# psu.net
KiCad netlist of a schematic drawn in EAGLE
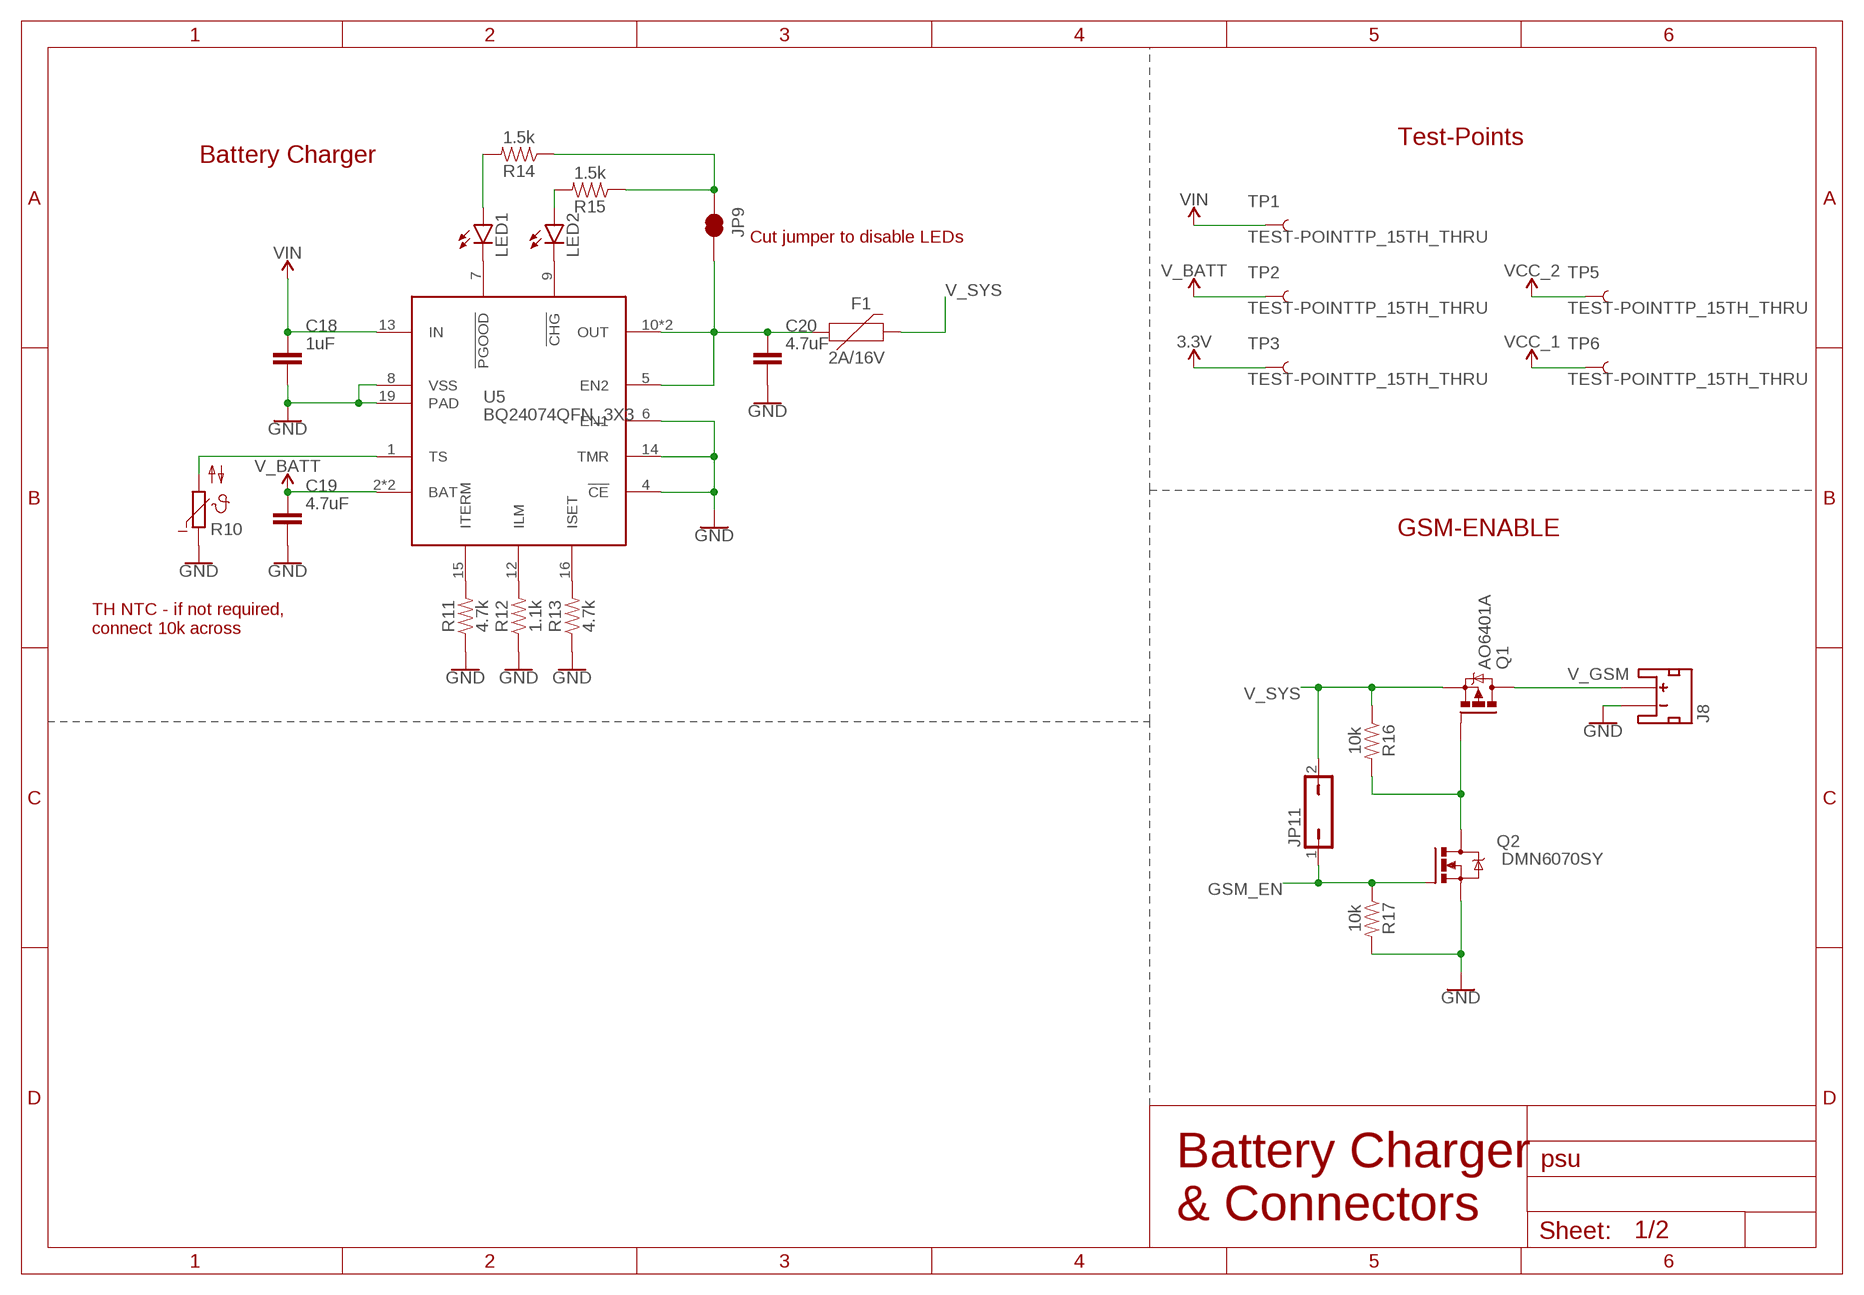
[diagram p0: schematic, sheet 1]
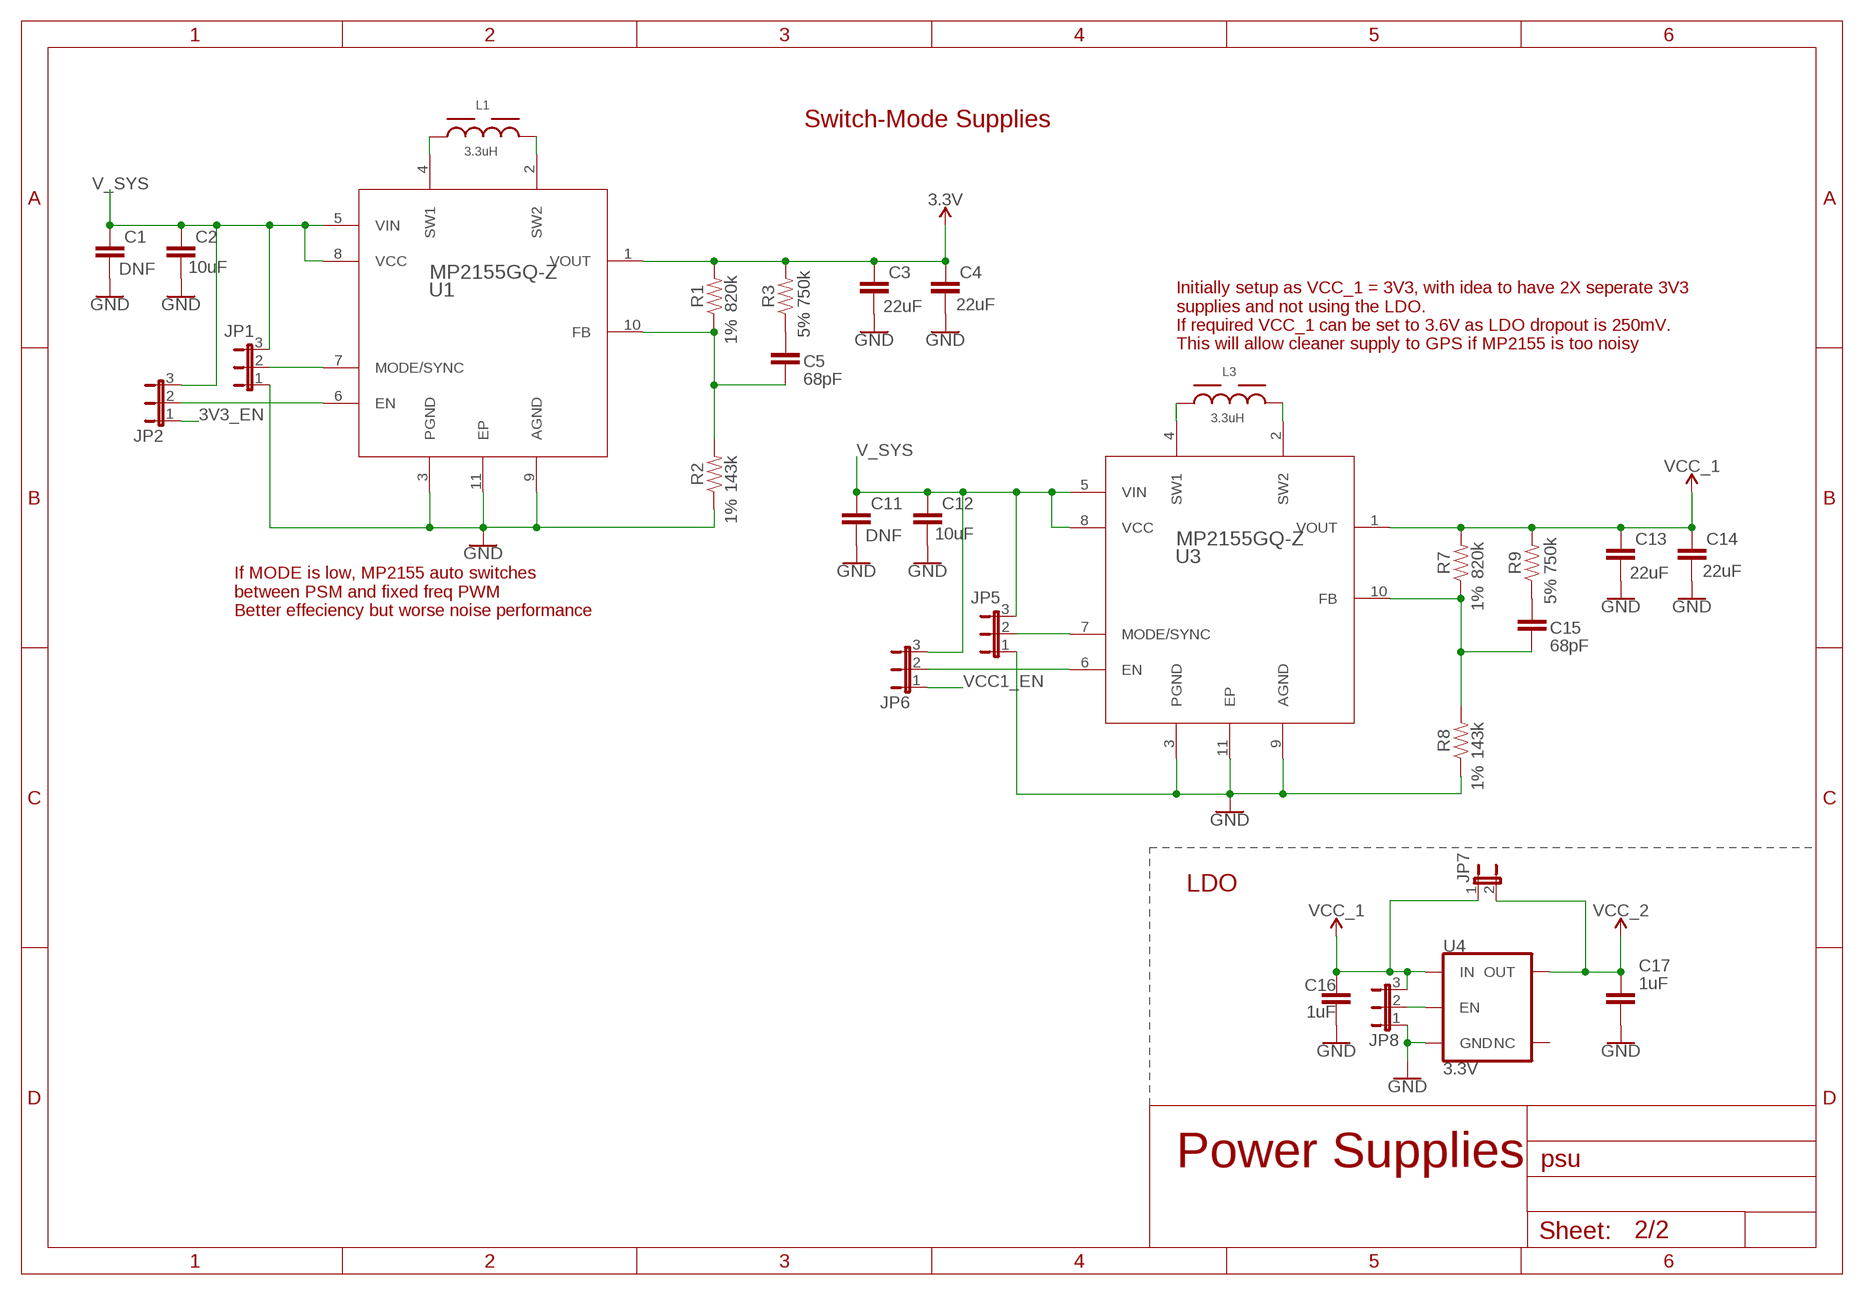
[diagram p1: schematic, sheet 2]

(export (version "E")
  (design (tool "Eeschema 10.0.6"))
  (components
    (comp (ref "C18")
      (value "1uF")
      (footprint "eagle-import:CAPC2012X110")
      (libsource (lib "eagle-import") (part "CCHIP-0805(2012-METRIC)_"))
    )
    (comp (ref "C19")
      (value "4.7uF")
      (footprint "eagle-import:CAPC2012X110")
      (libsource (lib "eagle-import") (part "CCHIP-0805(2012-METRIC)_"))
    )
    (comp (ref "C20")
      (value "4.7uF")
      (footprint "eagle-import:CAPC2012X110")
      (libsource (lib "eagle-import") (part "CCHIP-0805(2012-METRIC)_"))
    )
    (comp (ref "F1")
      (value "2A/16V")
      (footprint "eagle-import:F1812")
      (libsource (lib "eagle-import") (part "PPTC_2A"))
    )
    (comp (ref "J8")
      (value "JST_2MM_MALE")
      (footprint "eagle-import:JST-2-SMD")
      (libsource (lib "eagle-import") (part "JST_2MM_MALE"))
    )
    (comp (ref "JP9")
      (value "JUMPER-SMT_2_NC_TRACE_SILK")
      (footprint "eagle-import:SMT-JUMPER_2_NC_TRACE_SILK")
      (libsource (lib "eagle-import") (part "JUMPER-SMT_2_NC_TRACE_SILK"))
    )
    (comp (ref "JP11")
      (value "JP1Q")
      (footprint "eagle-import:JP1")
      (libsource (lib "eagle-import") (part "JP1Q"))
    )
    (comp (ref "LED1")
      (value "LEDSML0805")
      (footprint "eagle-import:SML0805")
      (libsource (lib "eagle-import") (part "LEDSML0805"))
    )
    (comp (ref "LED2")
      (value "LEDSML0805")
      (footprint "eagle-import:SML0805")
      (libsource (lib "eagle-import") (part "LEDSML0805"))
    )
    (comp (ref "Q1")
      (value "AO6401A")
      (footprint "eagle-import:TSOP-6")
      (libsource (lib "eagle-import") (part "AO6401A"))
    )
    (comp (ref "Q2")
      (value "DMN6070SY")
      (footprint "eagle-import:SOT-89-3")
      (libsource (lib "eagle-import") (part "DMN6070SY-13"))
    )
    (comp (ref "R10")
      (value "DNF")
      (footprint "eagle-import:P640")
      (libsource (lib "eagle-import") (part "NTC640"))
    )
    (comp (ref "R11")
      (value "4.7k")
      (footprint "eagle-import:0603")
      (libsource (lib "eagle-import") (part "RESISTOR0603"))
    )
    (comp (ref "R12")
      (value "1.1k")
      (footprint "eagle-import:0603")
      (libsource (lib "eagle-import") (part "RESISTOR0603"))
    )
    (comp (ref "R13")
      (value "4.7k")
      (footprint "eagle-import:0603")
      (libsource (lib "eagle-import") (part "RESISTOR0603"))
    )
    (comp (ref "R14")
      (value "1.5k")
      (footprint "eagle-import:0603")
      (libsource (lib "eagle-import") (part "RESISTOR0603"))
    )
    (comp (ref "R15")
      (value "1.5k")
      (footprint "eagle-import:0603")
      (libsource (lib "eagle-import") (part "RESISTOR0603"))
    )
    (comp (ref "R16")
      (value "10k")
      (footprint "eagle-import:0603")
      (libsource (lib "eagle-import") (part "RESISTOR0603"))
    )
    (comp (ref "R17")
      (value "10k")
      (footprint "eagle-import:0603")
      (libsource (lib "eagle-import") (part "RESISTOR0603"))
    )
    (comp (ref "TP1")
      (value "TEST-POINTTP_15TH_THRU")
      (footprint "eagle-import:TP_15TH")
      (libsource (lib "eagle-import") (part "TEST-POINTTP_15TH_THRU"))
    )
    (comp (ref "TP2")
      (value "TEST-POINTTP_15TH_THRU")
      (footprint "eagle-import:TP_15TH")
      (libsource (lib "eagle-import") (part "TEST-POINTTP_15TH_THRU"))
    )
    (comp (ref "TP3")
      (value "TEST-POINTTP_15TH_THRU")
      (footprint "eagle-import:TP_15TH")
      (libsource (lib "eagle-import") (part "TEST-POINTTP_15TH_THRU"))
    )
    (comp (ref "TP5")
      (value "TEST-POINTTP_15TH_THRU")
      (footprint "eagle-import:TP_15TH")
      (libsource (lib "eagle-import") (part "TEST-POINTTP_15TH_THRU"))
    )
    (comp (ref "TP6")
      (value "TEST-POINTTP_15TH_THRU")
      (footprint "eagle-import:TP_15TH")
      (libsource (lib "eagle-import") (part "TEST-POINTTP_15TH_THRU"))
    )
    (comp (ref "U5")
      (value "BQ24074QFN_3X3")
      (footprint "eagle-import:QFN_3X3")
      (libsource (lib "eagle-import") (part "BQ24074QFN_3X3"))
    )
    (comp (ref "C1")
      (value "DNF")
      (footprint "eagle-import:CAPC2012X110")
      (libsource (lib "eagle-import") (part "CCHIP-0805(2012-METRIC)_"))
    )
    (comp (ref "C2")
      (value "10uF")
      (footprint "eagle-import:CAPC2012X110")
      (fields (field (name "TYPE") "X7R") (field (name "VOLTAGE_RATING") "6.3V"))
      (libsource (lib "eagle-import") (part "CCHIP-0805(2012-METRIC)_"))
    )
    (comp (ref "C3")
      (value "22uF")
      (footprint "eagle-import:CAPC2012X110")
      (fields (field (name "TYPE") "X5R") (field (name "VOLTAGE_RATING") "10V"))
      (libsource (lib "eagle-import") (part "CCHIP-0805(2012-METRIC)_"))
    )
    (comp (ref "C4")
      (value "22uF")
      (footprint "eagle-import:CAPC2012X110")
      (fields (field (name "TYPE") "X5R") (field (name "VOLTAGE_RATING") "10V"))
      (libsource (lib "eagle-import") (part "CCHIP-0805(2012-METRIC)_"))
    )
    (comp (ref "C5")
      (value "68pF")
      (footprint "eagle-import:CAPC1608X85")
      (fields (field (name "TYPE") "X7R") (field (name "VOLTAGE_RATING") "50V"))
      (libsource (lib "eagle-import") (part "CCHIP-0603(1608-METRIC)_"))
    )
    (comp (ref "C11")
      (value "DNF")
      (footprint "eagle-import:CAPC2012X110")
      (libsource (lib "eagle-import") (part "CCHIP-0805(2012-METRIC)_"))
    )
    (comp (ref "C12")
      (value "10uF")
      (footprint "eagle-import:CAPC2012X110")
      (fields (field (name "TYPE") "X7R") (field (name "VOLTAGE_RATING") "6.3V"))
      (libsource (lib "eagle-import") (part "CCHIP-0805(2012-METRIC)_"))
    )
    (comp (ref "C13")
      (value "22uF")
      (footprint "eagle-import:CAPC2012X110")
      (fields (field (name "TYPE") "X5R") (field (name "VOLTAGE_RATING") "10V"))
      (libsource (lib "eagle-import") (part "CCHIP-0805(2012-METRIC)_"))
    )
    (comp (ref "C14")
      (value "22uF")
      (footprint "eagle-import:CAPC2012X110")
      (fields (field (name "TYPE") "X5R") (field (name "VOLTAGE_RATING") "10V"))
      (libsource (lib "eagle-import") (part "CCHIP-0805(2012-METRIC)_"))
    )
    (comp (ref "C15")
      (value "68pF")
      (footprint "eagle-import:CAPC1608X85")
      (fields (field (name "TYPE") "X7R") (field (name "VOLTAGE_RATING") "50V"))
      (libsource (lib "eagle-import") (part "CCHIP-0603(1608-METRIC)_"))
    )
    (comp (ref "C16")
      (value "1uF")
      (footprint "eagle-import:CAPC2012X110")
      (libsource (lib "eagle-import") (part "CCHIP-0805(2012-METRIC)_"))
    )
    (comp (ref "C17")
      (value "1uF")
      (footprint "eagle-import:CAPC2012X110")
      (libsource (lib "eagle-import") (part "CCHIP-0805(2012-METRIC)_"))
    )
    (comp (ref "JP1")
      (value "JP2E")
      (footprint "eagle-import:JP2")
      (libsource (lib "eagle-import") (part "JP2E"))
    )
    (comp (ref "JP2")
      (value "JP2E")
      (footprint "eagle-import:JP2")
      (libsource (lib "eagle-import") (part "JP2E"))
    )
    (comp (ref "JP5")
      (value "JP2E")
      (footprint "eagle-import:JP2")
      (libsource (lib "eagle-import") (part "JP2E"))
    )
    (comp (ref "JP6")
      (value "JP2E")
      (footprint "eagle-import:JP2")
      (libsource (lib "eagle-import") (part "JP2E"))
    )
    (comp (ref "JP7")
      (value "JP1E")
      (footprint "eagle-import:JP1")
      (libsource (lib "eagle-import") (part "JP1E"))
    )
    (comp (ref "JP8")
      (value "JP2E")
      (footprint "eagle-import:JP2")
      (libsource (lib "eagle-import") (part "JP2E"))
    )
    (comp (ref "L1")
      (value "3.3uH")
      (footprint "eagle-import:WE-HCI_7050")
      (libsource (lib "eagle-import") (part "WE-HCI_7050_744314330"))
    )
    (comp (ref "L3")
      (value "3.3uH")
      (footprint "eagle-import:WE-HCI_7050")
      (libsource (lib "eagle-import") (part "WE-HCI_7050_744314330"))
    )
    (comp (ref "R1")
      (value "820k")
      (footprint "eagle-import:0603")
      (fields (field (name "TOLERANCE") "1%"))
      (libsource (lib "eagle-import") (part "RESISTOR0603"))
    )
    (comp (ref "R2")
      (value "143k")
      (footprint "eagle-import:0603")
      (fields (field (name "TOLERANCE") "1%"))
      (libsource (lib "eagle-import") (part "RESISTOR0603"))
    )
    (comp (ref "R3")
      (value "750k")
      (footprint "eagle-import:0603")
      (fields (field (name "TOLERANCE") "5%"))
      (libsource (lib "eagle-import") (part "RESISTOR0603"))
    )
    (comp (ref "R7")
      (value "820k")
      (footprint "eagle-import:0603")
      (fields (field (name "TOLERANCE") "1%"))
      (libsource (lib "eagle-import") (part "RESISTOR0603"))
    )
    (comp (ref "R8")
      (value "143k")
      (footprint "eagle-import:0603")
      (fields (field (name "TOLERANCE") "1%"))
      (libsource (lib "eagle-import") (part "RESISTOR0603"))
    )
    (comp (ref "R9")
      (value "750k")
      (footprint "eagle-import:0603")
      (fields (field (name "TOLERANCE") "5%"))
      (libsource (lib "eagle-import") (part "RESISTOR0603"))
    )
    (comp (ref "U1")
      (value "MP2155GQ-Z")
      (footprint "eagle-import:QFN-10_MP2155_MNP")
      (fields (field (name "COPYRIGHT") "Copyright (C) 2022 Ultra Librarian. All rights reserved."))
      (libsource (lib "eagle-import") (part "MP2155GQ-Z"))
    )
    (comp (ref "U3")
      (value "MP2155GQ-Z")
      (footprint "eagle-import:QFN-10_MP2155_MNP")
      (fields (field (name "COPYRIGHT") "Copyright (C) 2022 Ultra Librarian. All rights reserved."))
      (libsource (lib "eagle-import") (part "MP2155GQ-Z"))
    )
    (comp (ref "U4")
      (value "3.3V")
      (footprint "eagle-import:SOT23-5")
      (libsource (lib "eagle-import") (part "V_REG_AP2112K-3.3V"))
    )
  )
  (nets
    (net (code "1") (name "3.3V") (class "Default")
      (node (ref "C3") (pin "1") (pinfunction "1_1") (pintype "passive"))
      (node (ref "C4") (pin "1") (pinfunction "1_1") (pintype "passive"))
      (node (ref "R1") (pin "2") (pinfunction "2_2") (pintype "passive"))
      (node (ref "R3") (pin "2") (pinfunction "2_2") (pintype "passive"))
      (node (ref "TP3") (pin "P$1") (pinfunction "1_P$1") (pintype "bidirectional"))
      (node (ref "U1") (pin "1") (pinfunction "VOUT_1") (pintype "power_in"))
    )
    (net (code "2") (name "3V3_EN") (class "Default")
      (node (ref "JP2") (pin "1") (pinfunction "1_1") (pintype "passive"))
    )
    (net (code "3") (name "GND") (class "Default")
      (node (ref "C1") (pin "2") (pinfunction "2_2") (pintype "passive"))
      (node (ref "C11") (pin "2") (pinfunction "2_2") (pintype "passive"))
      (node (ref "C12") (pin "2") (pinfunction "2_2") (pintype "passive"))
      (node (ref "C13") (pin "2") (pinfunction "2_2") (pintype "passive"))
      (node (ref "C14") (pin "2") (pinfunction "2_2") (pintype "passive"))
      (node (ref "C16") (pin "2") (pinfunction "2_2") (pintype "passive"))
      (node (ref "C17") (pin "2") (pinfunction "2_2") (pintype "passive"))
      (node (ref "C18") (pin "2") (pinfunction "2_2") (pintype "passive"))
      (node (ref "C19") (pin "2") (pinfunction "2_2") (pintype "passive"))
      (node (ref "C2") (pin "2") (pinfunction "2_2") (pintype "passive"))
      (node (ref "C20") (pin "2") (pinfunction "2_2") (pintype "passive"))
      (node (ref "C3") (pin "2") (pinfunction "2_2") (pintype "passive"))
      (node (ref "C4") (pin "2") (pinfunction "2_2") (pintype "passive"))
      (node (ref "J8") (pin "1") (pinfunction "-_1") (pintype "bidirectional"))
      (node (ref "JP1") (pin "1") (pinfunction "1_1") (pintype "passive"))
      (node (ref "JP5") (pin "1") (pinfunction "1_1") (pintype "passive"))
      (node (ref "JP8") (pin "1") (pinfunction "1_1") (pintype "passive"))
      (node (ref "Q2") (pin "3") (pinfunction "S_3") (pintype "passive"))
      (node (ref "R10") (pin "1") (pinfunction "1_1") (pintype "passive"))
      (node (ref "R11") (pin "1") (pinfunction "1_1") (pintype "passive"))
      (node (ref "R12") (pin "1") (pinfunction "1_1") (pintype "passive"))
      (node (ref "R13") (pin "1") (pinfunction "1_1") (pintype "passive"))
      (node (ref "R17") (pin "2") (pinfunction "2_2") (pintype "passive"))
      (node (ref "R2") (pin "1") (pinfunction "1_1") (pintype "passive"))
      (node (ref "R8") (pin "1") (pinfunction "1_1") (pintype "passive"))
      (node (ref "U1") (pin "11") (pinfunction "EP_11") (pintype "power_in"))
      (node (ref "U1") (pin "3") (pinfunction "PGND_3") (pintype "power_in"))
      (node (ref "U1") (pin "9") (pinfunction "AGND_9") (pintype "passive"))
      (node (ref "U3") (pin "11") (pinfunction "EP_11") (pintype "power_in"))
      (node (ref "U3") (pin "3") (pinfunction "PGND_3") (pintype "power_in"))
      (node (ref "U3") (pin "9") (pinfunction "AGND_9") (pintype "passive"))
      (node (ref "U4") (pin "2") (pinfunction "GND_2") (pintype "input"))
      (node (ref "U5") (pin "14") (pinfunction "TMR_14") (pintype "bidirectional"))
      (node (ref "U5") (pin "19") (pinfunction "PAD_19") (pintype "bidirectional"))
      (node (ref "U5") (pin "4") (pinfunction "~{CE}_4") (pintype "bidirectional"))
      (node (ref "U5") (pin "6") (pinfunction "EN1_6") (pintype "bidirectional"))
      (node (ref "U5") (pin "8") (pinfunction "VSS_8") (pintype "bidirectional"))
    )
    (net (code "4") (name "GSM_EN") (class "Default")
      (node (ref "JP11") (pin "1") (pinfunction "1_1") (pintype "passive"))
      (node (ref "Q2") (pin "1") (pinfunction "G_1") (pintype "passive"))
      (node (ref "R17") (pin "1") (pinfunction "1_1") (pintype "passive"))
    )
    (net (code "5") (name "Net-(C5-Pad1)") (class "Default")
      (node (ref "C5") (pin "1") (pinfunction "1_1") (pintype "passive"))
      (node (ref "R3") (pin "1") (pinfunction "1_1") (pintype "passive"))
    )
    (net (code "6") (name "Net-(C15-Pad1)") (class "Default")
      (node (ref "C15") (pin "1") (pinfunction "1_1") (pintype "passive"))
      (node (ref "R9") (pin "1") (pinfunction "1_1") (pintype "passive"))
    )
    (net (code "7") (name "Net-(JP9-Pad1)") (class "Default")
      (node (ref "JP9") (pin "1") (pinfunction "1_1") (pintype "passive"))
      (node (ref "R14") (pin "1") (pinfunction "1_1") (pintype "passive"))
      (node (ref "R15") (pin "1") (pinfunction "1_1") (pintype "passive"))
    )
    (net (code "8") (name "Net-(LED1-PadA)") (class "Default")
      (node (ref "LED1") (pin "A") (pinfunction "A_A") (pintype "passive"))
      (node (ref "R14") (pin "2") (pinfunction "2_2") (pintype "passive"))
    )
    (net (code "9") (name "Net-(LED2-PadA)") (class "Default")
      (node (ref "LED2") (pin "A") (pinfunction "A_A") (pintype "passive"))
      (node (ref "R15") (pin "2") (pinfunction "2_2") (pintype "passive"))
    )
    (net (code "10") (name "Net-(Q1-G)") (class "Default")
      (node (ref "Q1") (pin "3") (pinfunction "G_3") (pintype "passive"))
      (node (ref "Q2") (pin "2") (pinfunction "D_2") (pintype "passive"))
      (node (ref "Q2") (pin "4") (pinfunction "D_4") (pintype "passive"))
      (node (ref "R16") (pin "2") (pinfunction "2_2") (pintype "passive"))
    )
    (net (code "11") (name "Net-(U1-EN)") (class "Default")
      (node (ref "JP2") (pin "2") (pinfunction "2_2") (pintype "passive"))
      (node (ref "U1") (pin "6") (pinfunction "EN_6") (pintype "passive"))
    )
    (net (code "12") (name "Net-(U1-FB)") (class "Default")
      (node (ref "C5") (pin "2") (pinfunction "2_2") (pintype "passive"))
      (node (ref "R1") (pin "1") (pinfunction "1_1") (pintype "passive"))
      (node (ref "R2") (pin "2") (pinfunction "2_2") (pintype "passive"))
      (node (ref "U1") (pin "10") (pinfunction "FB_10") (pintype "passive"))
    )
    (net (code "13") (name "Net-(U1-MODE{slash}SYNC)") (class "Default")
      (node (ref "JP1") (pin "2") (pinfunction "2_2") (pintype "passive"))
      (node (ref "U1") (pin "7") (pinfunction "MODE/SYNC_7") (pintype "passive"))
    )
    (net (code "14") (name "Net-(U1-SW1)") (class "Default")
      (node (ref "L1") (pin "1") (pinfunction "1_1") (pintype "passive"))
      (node (ref "U1") (pin "4") (pinfunction "SW1_4") (pintype "passive"))
    )
    (net (code "15") (name "Net-(U1-SW2)") (class "Default")
      (node (ref "L1") (pin "2") (pinfunction "2_2") (pintype "passive"))
      (node (ref "U1") (pin "2") (pinfunction "SW2_2") (pintype "output"))
    )
    (net (code "16") (name "Net-(U3-EN)") (class "Default")
      (node (ref "JP6") (pin "2") (pinfunction "2_2") (pintype "passive"))
      (node (ref "U3") (pin "6") (pinfunction "EN_6") (pintype "passive"))
    )
    (net (code "17") (name "Net-(U3-FB)") (class "Default")
      (node (ref "C15") (pin "2") (pinfunction "2_2") (pintype "passive"))
      (node (ref "R7") (pin "1") (pinfunction "1_1") (pintype "passive"))
      (node (ref "R8") (pin "2") (pinfunction "2_2") (pintype "passive"))
      (node (ref "U3") (pin "10") (pinfunction "FB_10") (pintype "passive"))
    )
    (net (code "18") (name "Net-(U3-MODE{slash}SYNC)") (class "Default")
      (node (ref "JP5") (pin "2") (pinfunction "2_2") (pintype "passive"))
      (node (ref "U3") (pin "7") (pinfunction "MODE/SYNC_7") (pintype "passive"))
    )
    (net (code "19") (name "Net-(U3-SW1)") (class "Default")
      (node (ref "L3") (pin "1") (pinfunction "1_1") (pintype "passive"))
      (node (ref "U3") (pin "4") (pinfunction "SW1_4") (pintype "passive"))
    )
    (net (code "20") (name "Net-(U3-SW2)") (class "Default")
      (node (ref "L3") (pin "2") (pinfunction "2_2") (pintype "passive"))
      (node (ref "U3") (pin "2") (pinfunction "SW2_2") (pintype "output"))
    )
    (net (code "21") (name "Net-(U4-EN)") (class "Default")
      (node (ref "JP8") (pin "2") (pinfunction "2_2") (pintype "passive"))
      (node (ref "U4") (pin "3") (pinfunction "EN_3") (pintype "input"))
    )
    (net (code "22") (name "Net-(U5-EN2)") (class "Default")
      (node (ref "C20") (pin "1") (pinfunction "1_1") (pintype "passive"))
      (node (ref "F1") (pin "1") (pinfunction "1_1") (pintype "bidirectional"))
      (node (ref "JP9") (pin "2") (pinfunction "2_2") (pintype "passive"))
      (node (ref "U5") (pin "10") (pinfunction "OUT_10") (pintype "bidirectional"))
      (node (ref "U5") (pin "11") (pinfunction "OUT_11") (pintype "bidirectional"))
      (node (ref "U5") (pin "5") (pinfunction "EN2_5") (pintype "bidirectional"))
    )
    (net (code "23") (name "Net-(U5-ILM)") (class "Default")
      (node (ref "R12") (pin "2") (pinfunction "2_2") (pintype "passive"))
      (node (ref "U5") (pin "12") (pinfunction "ILM_12") (pintype "bidirectional"))
    )
    (net (code "24") (name "Net-(U5-ISET)") (class "Default")
      (node (ref "R13") (pin "2") (pinfunction "2_2") (pintype "passive"))
      (node (ref "U5") (pin "16") (pinfunction "ISET_16") (pintype "bidirectional"))
    )
    (net (code "25") (name "Net-(U5-ITERM)") (class "Default")
      (node (ref "R11") (pin "2") (pinfunction "2_2") (pintype "passive"))
      (node (ref "U5") (pin "15") (pinfunction "ITERM_15") (pintype "bidirectional"))
    )
    (net (code "26") (name "Net-(U5-TS)") (class "Default")
      (node (ref "R10") (pin "2") (pinfunction "2_2") (pintype "passive"))
      (node (ref "U5") (pin "1") (pinfunction "TS_1") (pintype "bidirectional"))
    )
    (net (code "27") (name "Net-(U5-~{CHG})") (class "Default")
      (node (ref "LED2") (pin "C") (pinfunction "C_C") (pintype "passive"))
      (node (ref "U5") (pin "9") (pinfunction "~{CHG}_9") (pintype "bidirectional"))
    )
    (net (code "28") (name "Net-(U5-~{PGOOD})") (class "Default")
      (node (ref "LED1") (pin "C") (pinfunction "C_C") (pintype "passive"))
      (node (ref "U5") (pin "7") (pinfunction "~{PGOOD}_7") (pintype "bidirectional"))
    )
    (net (code "29") (name "VCC1_EN") (class "Default")
      (node (ref "JP6") (pin "1") (pinfunction "1_1") (pintype "passive"))
    )
    (net (code "30") (name "VCC_1") (class "Default")
      (node (ref "C13") (pin "1") (pinfunction "1_1") (pintype "passive"))
      (node (ref "C14") (pin "1") (pinfunction "1_1") (pintype "passive"))
      (node (ref "C16") (pin "1") (pinfunction "1_1") (pintype "passive"))
      (node (ref "JP7") (pin "1") (pinfunction "1_1") (pintype "passive"))
      (node (ref "JP8") (pin "3") (pinfunction "3_3") (pintype "passive"))
      (node (ref "R7") (pin "2") (pinfunction "2_2") (pintype "passive"))
      (node (ref "R9") (pin "2") (pinfunction "2_2") (pintype "passive"))
      (node (ref "TP6") (pin "P$1") (pinfunction "1_P$1") (pintype "bidirectional"))
      (node (ref "U3") (pin "1") (pinfunction "VOUT_1") (pintype "power_in"))
      (node (ref "U4") (pin "1") (pinfunction "IN_1") (pintype "input"))
    )
    (net (code "31") (name "VCC_2") (class "Default")
      (node (ref "C17") (pin "1") (pinfunction "1_1") (pintype "passive"))
      (node (ref "JP7") (pin "2") (pinfunction "2_2") (pintype "passive"))
      (node (ref "TP5") (pin "P$1") (pinfunction "1_P$1") (pintype "bidirectional"))
      (node (ref "U4") (pin "5") (pinfunction "OUT_5") (pintype "passive"))
    )
    (net (code "32") (name "VIN") (class "Default")
      (node (ref "C18") (pin "1") (pinfunction "1_1") (pintype "passive"))
      (node (ref "TP1") (pin "P$1") (pinfunction "1_P$1") (pintype "bidirectional"))
      (node (ref "U5") (pin "13") (pinfunction "IN_13") (pintype "bidirectional"))
    )
    (net (code "33") (name "V_BATT") (class "Default")
      (node (ref "C19") (pin "1") (pinfunction "1_1") (pintype "passive"))
      (node (ref "TP2") (pin "P$1") (pinfunction "1_P$1") (pintype "bidirectional"))
      (node (ref "U5") (pin "2") (pinfunction "BAT_2") (pintype "bidirectional"))
      (node (ref "U5") (pin "3") (pinfunction "BAT_3") (pintype "bidirectional"))
    )
    (net (code "34") (name "V_GSM") (class "Default")
      (node (ref "J8") (pin "2") (pinfunction "+_2") (pintype "bidirectional"))
      (node (ref "Q1") (pin "1") (pinfunction "D_1") (pintype "passive"))
      (node (ref "Q1") (pin "2") (pinfunction "D_2") (pintype "passive"))
      (node (ref "Q1") (pin "5") (pinfunction "D_5") (pintype "passive"))
      (node (ref "Q1") (pin "6") (pinfunction "D_6") (pintype "passive"))
    )
    (net (code "35") (name "V_SYS") (class "Default")
      (node (ref "C1") (pin "1") (pinfunction "1_1") (pintype "passive"))
      (node (ref "C11") (pin "1") (pinfunction "1_1") (pintype "passive"))
      (node (ref "C12") (pin "1") (pinfunction "1_1") (pintype "passive"))
      (node (ref "C2") (pin "1") (pinfunction "1_1") (pintype "passive"))
      (node (ref "F1") (pin "2") (pinfunction "2_2") (pintype "bidirectional"))
      (node (ref "JP1") (pin "3") (pinfunction "3_3") (pintype "passive"))
      (node (ref "JP11") (pin "2") (pinfunction "2_2") (pintype "passive"))
      (node (ref "JP2") (pin "3") (pinfunction "3_3") (pintype "passive"))
      (node (ref "JP5") (pin "3") (pinfunction "3_3") (pintype "passive"))
      (node (ref "JP6") (pin "3") (pinfunction "3_3") (pintype "passive"))
      (node (ref "Q1") (pin "4") (pinfunction "S_4") (pintype "passive"))
      (node (ref "R16") (pin "1") (pinfunction "1_1") (pintype "passive"))
      (node (ref "U1") (pin "5") (pinfunction "VIN_5") (pintype "power_in"))
      (node (ref "U1") (pin "8") (pinfunction "VCC_8") (pintype "power_in"))
      (node (ref "U3") (pin "5") (pinfunction "VIN_5") (pintype "power_in"))
      (node (ref "U3") (pin "8") (pinfunction "VCC_8") (pintype "power_in"))
    )
    (net (code "36") (name "unconnected-(J8-PAD1-PadNC1)") (class "Default")
      (node (ref "J8") (pin "NC1") (pinfunction "PAD1_NC1") (pintype "bidirectional"))
    )
    (net (code "37") (name "unconnected-(J8-PAD2-PadNC2)") (class "Default")
      (node (ref "J8") (pin "NC2") (pinfunction "PAD2_NC2") (pintype "bidirectional"))
    )
    (net (code "38") (name "unconnected-(U4-NC-Pad4)") (class "Default")
      (node (ref "U4") (pin "4") (pinfunction "NC_4") (pintype "no_connect"))
    )
  )
)
